# IP6518C.net
KiCad netlist of a schematic drawn in Altium Designer
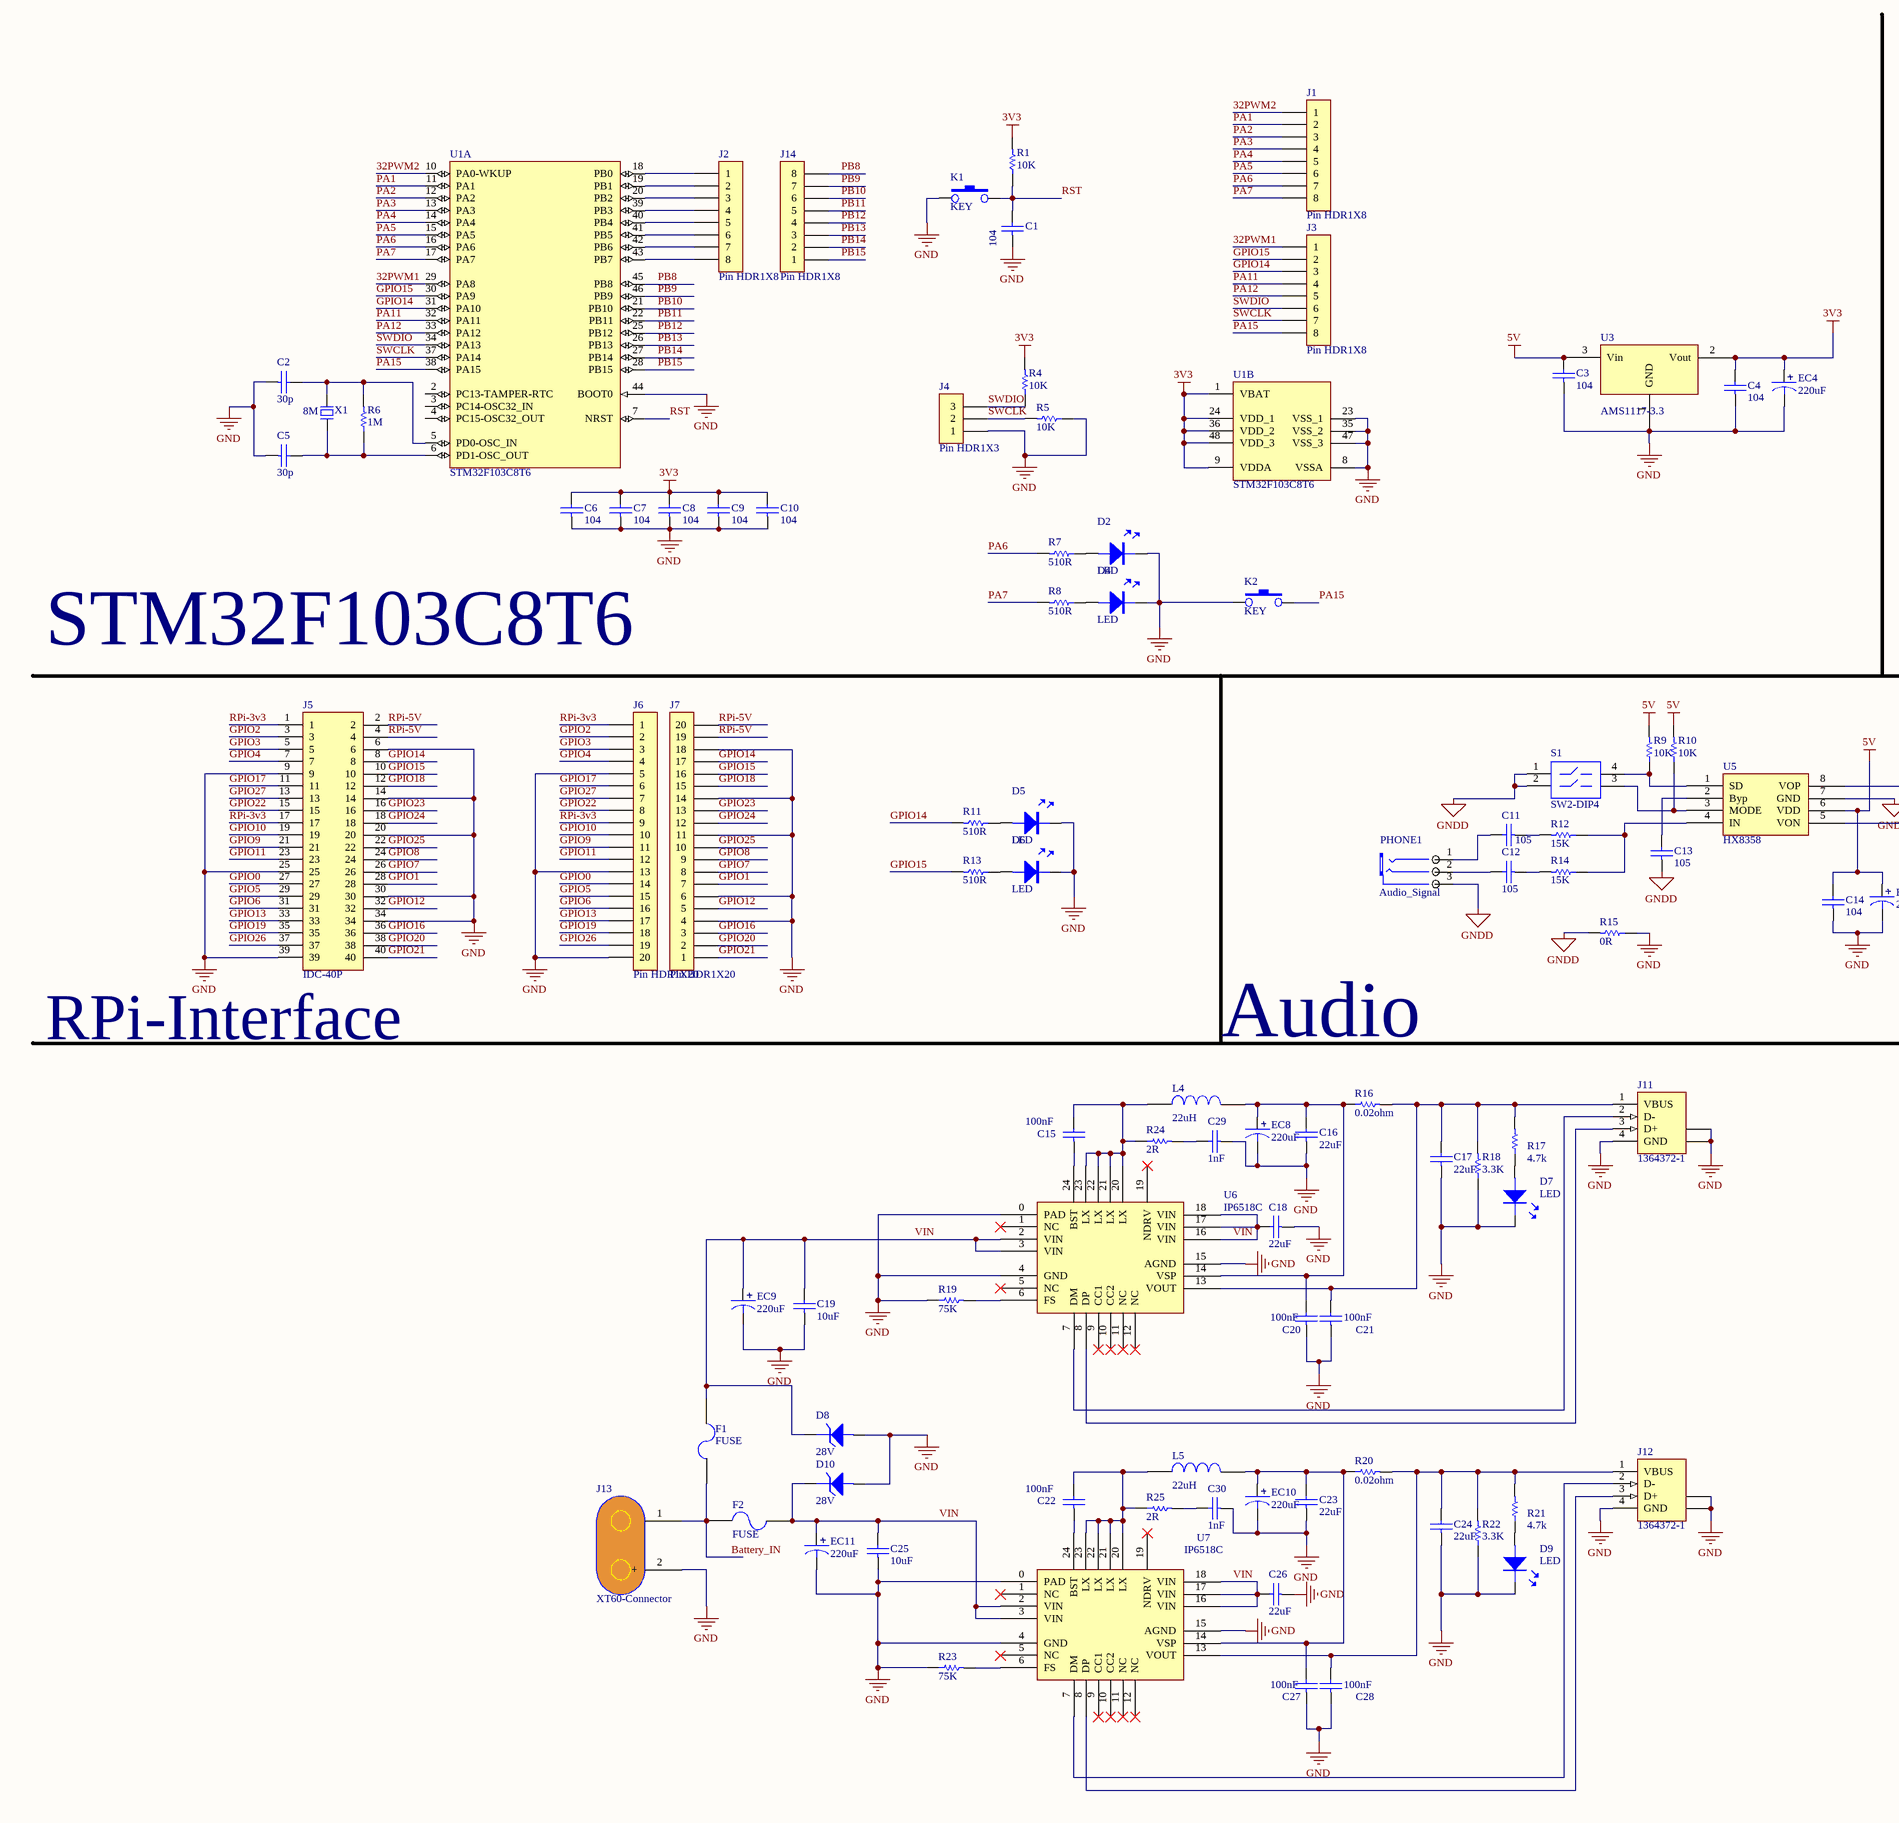
[diagram p0: IP6518C供电.SchDoc, left]
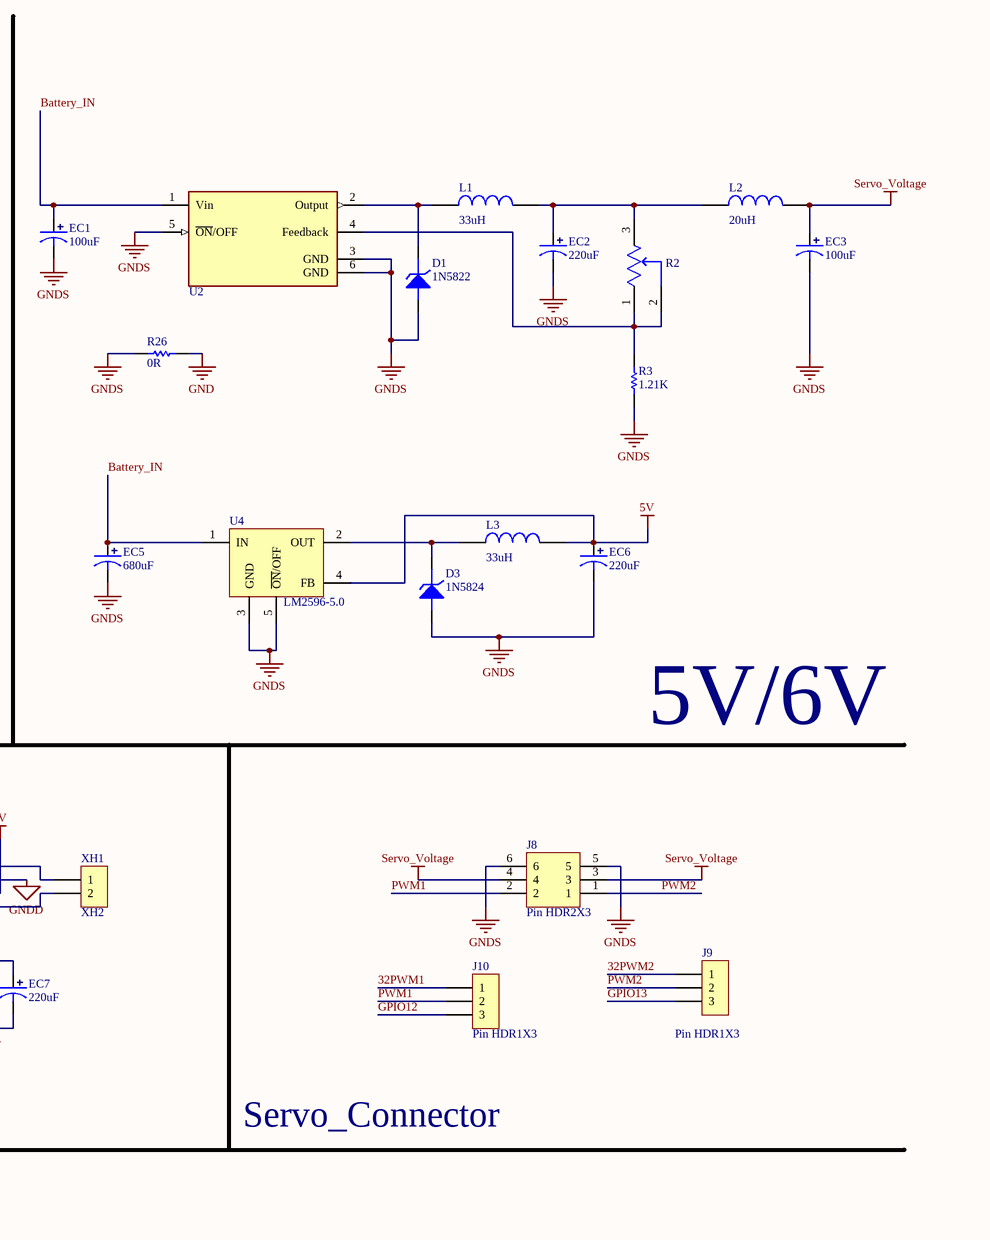
[diagram p1: IP6518C供电.SchDoc, right]

(export (version "E")
  (design (tool "Eeschema 10.0.6"))
  (components
    (comp (ref "C1")
      (value "104")
      (footprint "0805C")
      (description "无极性电容")
      (libsource (lib "电容") (part "CAP"))
    )
    (comp (ref "C2")
      (value "30p")
      (footprint "0805C")
      (description "无极性电容")
      (libsource (lib "电容") (part "CAP"))
    )
    (comp (ref "C3")
      (value "104")
      (footprint "0805C")
      (description "无极性电容")
      (libsource (lib "电容") (part "CAP"))
    )
    (comp (ref "C4")
      (value "104")
      (footprint "0805C")
      (description "无极性电容")
      (libsource (lib "电容") (part "CAP"))
    )
    (comp (ref "C5")
      (value "30p")
      (footprint "0805C")
      (description "无极性电容")
      (libsource (lib "电容") (part "CAP"))
    )
    (comp (ref "C6")
      (value "104")
      (footprint "0805C")
      (description "无极性电容")
      (libsource (lib "电容") (part "CAP"))
    )
    (comp (ref "C7")
      (value "104")
      (footprint "0805C")
      (description "无极性电容")
      (libsource (lib "电容") (part "CAP"))
    )
    (comp (ref "C8")
      (value "104")
      (footprint "0805C")
      (description "无极性电容")
      (libsource (lib "电容") (part "CAP"))
    )
    (comp (ref "C9")
      (value "104")
      (footprint "0805C")
      (description "无极性电容")
      (libsource (lib "电容") (part "CAP"))
    )
    (comp (ref "C10")
      (value "104")
      (footprint "0805C")
      (description "无极性电容")
      (libsource (lib "电容") (part "CAP"))
    )
    (comp (ref "C11")
      (value "105")
      (footprint "0805C")
      (description "无极性电容")
      (libsource (lib "电容") (part "CAP"))
    )
    (comp (ref "C12")
      (value "105")
      (footprint "0805C")
      (description "无极性电容")
      (libsource (lib "电容") (part "CAP"))
    )
    (comp (ref "C13")
      (value "105")
      (footprint "0805C")
      (description "无极性电容")
      (libsource (lib "电容") (part "CAP"))
    )
    (comp (ref "C14")
      (value "104")
      (footprint "0805C")
      (description "无极性电容")
      (libsource (lib "电容") (part "CAP"))
    )
    (comp (ref "C15")
      (value "100nF")
      (footprint "0805C")
      (description "无极性电容")
      (libsource (lib "电容") (part "CAP"))
    )
    (comp (ref "C16")
      (value "22uF")
      (footprint "1206C")
      (description "无极性电容")
      (libsource (lib "电容") (part "CAP"))
    )
    (comp (ref "C17")
      (value "22uF")
      (footprint "1206C")
      (description "无极性电容")
      (libsource (lib "电容") (part "CAP"))
    )
    (comp (ref "C18")
      (value "22uF")
      (footprint "1206C")
      (description "无极性电容")
      (libsource (lib "电容") (part "CAP"))
    )
    (comp (ref "C19")
      (value "10uF")
      (footprint "1206C")
      (description "无极性电容")
      (libsource (lib "电容") (part "CAP"))
    )
    (comp (ref "C20")
      (value "100nF")
      (footprint "0805C")
      (description "无极性电容")
      (libsource (lib "电容") (part "CAP"))
    )
    (comp (ref "C21")
      (value "100nF")
      (footprint "0805C")
      (description "无极性电容")
      (libsource (lib "电容") (part "CAP"))
    )
    (comp (ref "C22")
      (value "100nF")
      (footprint "0805C")
      (description "无极性电容")
      (libsource (lib "电容") (part "CAP"))
    )
    (comp (ref "C23")
      (value "22uF")
      (footprint "1206C")
      (description "无极性电容")
      (libsource (lib "电容") (part "CAP"))
    )
    (comp (ref "C24")
      (value "22uF")
      (footprint "1206C")
      (description "无极性电容")
      (libsource (lib "电容") (part "CAP"))
    )
    (comp (ref "C25")
      (value "10uF")
      (footprint "1206C")
      (description "无极性电容")
      (libsource (lib "电容") (part "CAP"))
    )
    (comp (ref "C26")
      (value "22uF")
      (footprint "1206C")
      (description "无极性电容")
      (libsource (lib "电容") (part "CAP"))
    )
    (comp (ref "C27")
      (value "100nF")
      (footprint "0805C")
      (description "无极性电容")
      (libsource (lib "电容") (part "CAP"))
    )
    (comp (ref "C28")
      (value "100nF")
      (footprint "0805C")
      (description "无极性电容")
      (libsource (lib "电容") (part "CAP"))
    )
    (comp (ref "C29")
      (value "1nF")
      (footprint "0805C")
      (description "无极性电容")
      (libsource (lib "电容") (part "CAP"))
    )
    (comp (ref "C30")
      (value "1nF")
      (footprint "0805C")
      (description "无极性电容")
      (libsource (lib "电容") (part "CAP"))
    )
    (comp (ref "D1")
      (value "1N5822")
      (footprint "SMA/DO-214AC")
      (description "稳压二极管")
      (libsource (lib "二极管") (part "DIODE ZENER"))
    )
    (comp (ref "D2") (value "LED") (footprint "LED-0805R") (libsource (lib "LED") (part "LED")))
    (comp (ref "D3")
      (value "1N5824")
      (footprint "SMA/DO-214AC")
      (description "稳压二极管")
      (libsource (lib "二极管") (part "DIODE ZENER"))
    )
    (comp (ref "D4") (value "LED") (footprint "LED-0805R") (libsource (lib "LED") (part "LED")))
    (comp (ref "D5") (value "LED") (footprint "LED-0805R") (libsource (lib "LED") (part "LED")))
    (comp (ref "D6") (value "LED") (footprint "LED-0805R") (libsource (lib "LED") (part "LED")))
    (comp (ref "D7") (value "LED") (footprint "LED-0805R") (libsource (lib "LED") (part "LED")))
    (comp (ref "D8")
      (value "28V")
      (footprint "SMA/DO-214AC")
      (description "稳压二极管")
      (libsource (lib "二极管") (part "DIODE ZENER"))
    )
    (comp (ref "D9") (value "LED") (footprint "LED-0805R") (libsource (lib "LED") (part "LED")))
    (comp (ref "D10")
      (value "28V")
      (footprint "SMA/DO-214AC")
      (description "稳压二极管")
      (libsource (lib "二极管") (part "DIODE ZENER"))
    )
    (comp (ref "EC1")
      (value "100uF")
      (footprint "SMD-EC6.3X6.3X10")
      (description "贴片电解电容")
      (libsource (lib "电容") (part "SMD_ECAP"))
    )
    (comp (ref "EC2")
      (value "220uF")
      (footprint "SMD-EC8X8X10")
      (description "贴片电解电容")
      (libsource (lib "电容") (part "SMD_ECAP"))
    )
    (comp (ref "EC3")
      (value "100uF")
      (footprint "SMD-EC6.3X6.3X10")
      (description "贴片电解电容")
      (libsource (lib "电容") (part "SMD_ECAP"))
    )
    (comp (ref "EC4")
      (value "220uF")
      (footprint "SMD-EC8X8X10")
      (description "贴片电解电容")
      (libsource (lib "电容") (part "SMD_ECAP"))
    )
    (comp (ref "EC5")
      (value "680uF")
      (footprint "DIP-EC10X17")
      (description "贴片电解电容")
      (libsource (lib "电容") (part "SMD_ECAP"))
    )
    (comp (ref "EC6")
      (value "220uF")
      (footprint "SMD-EC8X8X10")
      (description "贴片电解电容")
      (libsource (lib "电容") (part "SMD_ECAP"))
    )
    (comp (ref "EC7")
      (value "220uF")
      (footprint "SMD-EC8X8X10")
      (description "贴片电解电容")
      (libsource (lib "电容") (part "SMD_ECAP"))
    )
    (comp (ref "EC8")
      (value "220uF")
      (footprint "SMD-EC8X8X10")
      (description "贴片电解电容")
      (libsource (lib "电容") (part "SMD_ECAP"))
    )
    (comp (ref "EC9")
      (value "220uF")
      (footprint "SMD-EC10X10X10")
      (description "贴片电解电容")
      (libsource (lib "电容") (part "SMD_ECAP"))
    )
    (comp (ref "EC10")
      (value "220uF")
      (footprint "SMD-EC8X8X10")
      (description "贴片电解电容")
      (libsource (lib "电容") (part "SMD_ECAP"))
    )
    (comp (ref "EC11")
      (value "220uF")
      (footprint "SMD-EC10X10X10")
      (description "贴片电解电容")
      (libsource (lib "电容") (part "SMD_ECAP"))
    )
    (comp (ref "F1") (value "FUSE") (footprint "FUSE-1812") (libsource (lib "保险丝") (part "FUSE")))
    (comp (ref "F2") (value "FUSE") (footprint "FUSE-1812") (libsource (lib "保险丝") (part "FUSE")))
    (comp (ref "J1")
      (value "Pin HDR1X8")
      (footprint "Pin HDR1X8/2.54mm-S")
      (libsource (lib "排针") (part "Pin HDR1X8"))
    )
    (comp (ref "J2")
      (value "Pin HDR1X8")
      (footprint "Pin HDR1X8/2.54mm-S")
      (libsource (lib "排针") (part "Pin HDR1X8"))
    )
    (comp (ref "J3")
      (value "Pin HDR1X8")
      (footprint "Pin HDR1X8/2.54mm-S")
      (libsource (lib "排针") (part "Pin HDR1X8"))
    )
    (comp (ref "J4")
      (value "Pin HDR1X3")
      (footprint "Pin HDR1X3/2.54mm-S")
      (libsource (lib "排针") (part "Pin HDR1X3"))
    )
    (comp (ref "J5") (value "IDC-40P") (footprint "IDC2.54-40P") (libsource (lib "简易牛角座") (part "IDC-40P")))
    (comp (ref "J6")
      (value "Pin HDR1X20")
      (footprint "Pin HDR1X20/2.54mm-S")
      (libsource (lib "排针") (part "Pin HDR1X20"))
    )
    (comp (ref "J7")
      (value "Pin HDR1X20")
      (footprint "Pin HDR1X20/2.54mm-S")
      (libsource (lib "") (part "Pin HDR1X20_1"))
    )
    (comp (ref "J8")
      (value "Pin HDR2X3")
      (footprint "Pin HDR2X3/2.54mm-S")
      (libsource (lib "排针") (part "Pin HDR2X3"))
    )
    (comp (ref "J9")
      (value "Pin HDR1X3")
      (footprint "Pin HDR1X3/2.54mm-S")
      (libsource (lib "") (part "Pin HDR1X3_1"))
    )
    (comp (ref "J10")
      (value "Pin HDR1X3")
      (footprint "Pin HDR1X3/2.54mm-S")
      (libsource (lib "") (part "Pin HDR1X3_1"))
    )
    (comp (ref "J11")
      (value "1364372-1")
      (footprint "440068")
      (description "USB 1.1, Right Angle, Thru-Hole, A Type, Receptacle, 4 Position, Black")
      (fields (field (name "PUBLISHER") "Altium Limited"))
      (libsource (lib "USB") (part "1364372-1"))
    )
    (comp (ref "J12")
      (value "1364372-1")
      (footprint "440068")
      (description "USB 1.1, Right Angle, Thru-Hole, A Type, Receptacle, 4 Position, Black")
      (fields (field (name "PUBLISHER") "Altium Limited"))
      (libsource (lib "USB") (part "1364372-1"))
    )
    (comp (ref "J13")
      (value "XT60-Connector")
      (footprint "TX60PW-M20")
      (description "对于母头，+-对调")
      (libsource (lib "XT60") (part "Component_1"))
    )
    (comp (ref "J14")
      (value "Pin HDR1X8")
      (footprint "Pin HDR1X8/2.54mm-S")
      (libsource (lib "") (part "Pin HDR1X8_1"))
    )
    (comp (ref "K1") (value "KEY") (footprint "SMD-3X6X4.3") (libsource (lib "轻触开关") (part "KEY")))
    (comp (ref "K2") (value "KEY") (footprint "SMD-3X6X4.3") (libsource (lib "轻触开关") (part "KEY")))
    (comp (ref "L1")
      (value "33uH")
      (footprint "CDRH74")
      (description "INDUCTOR")
      (libsource (lib "电感") (part "INDUCTOR"))
    )
    (comp (ref "L2")
      (value "20uH")
      (footprint "CDRH74")
      (description "INDUCTOR")
      (libsource (lib "电感") (part "INDUCTOR"))
    )
    (comp (ref "L3")
      (value "33uH")
      (footprint "CDRH74")
      (description "INDUCTOR")
      (libsource (lib "电感") (part "INDUCTOR"))
    )
    (comp (ref "L4")
      (value "22uH")
      (footprint "CDRH127")
      (description "INDUCTOR")
      (libsource (lib "电感") (part "INDUCTOR"))
    )
    (comp (ref "L5")
      (value "22uH")
      (footprint "CDRH129")
      (description "INDUCTOR")
      (libsource (lib "电感") (part "INDUCTOR"))
    )
    (comp (ref "PHONE1")
      (value "Audio_Signal")
      (footprint "PHONE_ST")
      (libsource (lib "音频插座") (part "PHONE_M"))
    )
    (comp (ref "R1") (value "10K") (footprint "0805R") (libsource (lib "电阻") (part "RES")))
    (comp (ref "R2")
      (value "3296W-1-504LF 50K")
      (footprint "Bourns_3296W_MFG")
      (description "RES TRIMMER 50K OHM 0.5W PC PIN TOP")
      (fields (field (name "DIGIKEY PART NUMBER") "3296W-504LF-ND") (field (name "MANUFACTURER") "Bourns"))
      (libsource (lib "EEConcierge") (part "3296W-1-504LF"))
    )
    (comp (ref "R3") (value "1.21K") (footprint "0805R") (libsource (lib "电阻") (part "RES")))
    (comp (ref "R4") (value "10K") (footprint "0805R") (libsource (lib "电阻") (part "RES")))
    (comp (ref "R5") (value "10K") (footprint "0805R") (libsource (lib "电阻") (part "RES")))
    (comp (ref "R6") (value "1M") (footprint "0805R") (libsource (lib "电阻") (part "RES")))
    (comp (ref "R7") (value "510R") (footprint "0805R") (libsource (lib "电阻") (part "RES")))
    (comp (ref "R8") (value "510R") (footprint "0805R") (libsource (lib "电阻") (part "RES")))
    (comp (ref "R9") (value "10K") (footprint "0805R") (libsource (lib "电阻") (part "RES")))
    (comp (ref "R10") (value "10K") (footprint "0805R") (libsource (lib "电阻") (part "RES")))
    (comp (ref "R11") (value "510R") (footprint "0805R") (libsource (lib "电阻") (part "RES")))
    (comp (ref "R12") (value "15K") (footprint "0805R") (libsource (lib "电阻") (part "RES")))
    (comp (ref "R13") (value "510R") (footprint "0805R") (libsource (lib "电阻") (part "RES")))
    (comp (ref "R14") (value "15K") (footprint "0805R") (libsource (lib "电阻") (part "RES")))
    (comp (ref "R15") (value "0R") (footprint "0805R") (libsource (lib "电阻") (part "RES")))
    (comp (ref "R16") (value "0.02ohm") (footprint "1206R") (libsource (lib "电阻") (part "RES")))
    (comp (ref "R17") (value "4.7k") (footprint "0805R") (libsource (lib "电阻") (part "RES")))
    (comp (ref "R18") (value "3.3K") (footprint "0805R") (libsource (lib "电阻") (part "RES")))
    (comp (ref "R19") (value "75K") (footprint "0805R") (libsource (lib "电阻") (part "RES")))
    (comp (ref "R20") (value "0.02ohm") (footprint "1206R") (libsource (lib "电阻") (part "RES")))
    (comp (ref "R21") (value "4.7k") (footprint "0805R") (libsource (lib "电阻") (part "RES")))
    (comp (ref "R22") (value "3.3K") (footprint "0805R") (libsource (lib "电阻") (part "RES")))
    (comp (ref "R23") (value "75K") (footprint "0805R") (libsource (lib "电阻") (part "RES")))
    (comp (ref "R24") (value "2R") (footprint "0805R") (libsource (lib "电阻") (part "RES")))
    (comp (ref "R25") (value "2R") (footprint "0805R") (libsource (lib "电阻") (part "RES")))
    (comp (ref "R26") (value "0R") (footprint "0805R") (libsource (lib "电阻") (part "RES")))
    (comp (ref "S1") (value "SW2-DIP4") (footprint "DIP-Switch2") (libsource (lib "拨码开关") (part "SW2-DIP4")))
    (comp (ref "U1")
      (value "STM32F103C8T6")
      (footprint "STM-LQFP48_N")
      (libsource (lib "STMicroelectronics STM32 F1") (part "STM32F103C8T6"))
    )
    (comp (ref "U2")
      (value "LM2596DSADJG")
      (footprint "ON_Semiconductor_936A-02_MFG")
      (description "IC REG MULT CONFG ADJ 3A D2PAK-5")
      (fields
        (field (name "DIGIKEY PART NUMBER") "LM2596DSADJGOS-ND")
        (field (name "MANUFACTURER") "ON Semiconductor")
      )
      (libsource (lib "EEConcierge") (part "LM2596DSADJG"))
    )
    (comp (ref "U3")
      (value "AMS1117-3.3")
      (footprint "SOT223")
      (description "三端稳压芯片")
      (libsource (lib "电源芯片") (part "AMS1117"))
    )
    (comp (ref "U4")
      (value "LM2596-5.0")
      (footprint "TO263-5A")
      (description "DC降压芯片")
      (libsource (lib "电源芯片") (part "LM2596-5.0"))
    )
    (comp (ref "U5") (value "HX8358") (footprint "SOP8-9") (libsource (lib "HX8358") (part "HX8358")))
    (comp (ref "U6") (value "IP6518C") (footprint "QFN24") (libsource (lib "IP6518C") (part "IP6518C")))
    (comp (ref "U7") (value "IP6518C") (footprint "QFN24") (libsource (lib "IP6518C") (part "IP6518C")))
    (comp (ref "X1")
      (value "8M")
      (footprint "OSC HC-49SMD")
      (description "2脚无源脚晶振")
      (libsource (lib "晶振") (part "XTAL-2P"))
    )
    (comp (ref "XH1") (value "XH2") (footprint "XH2/2.54mm/90") (libsource (lib "XH，VH") (part "XH2")))
  )
  (nets
    (net (code "1") (name "/32PWM1") (class "Default")
      (node (ref "J10") (pin "1") (pinfunction "1_1") (pintype "passive"))
      (node (ref "J3") (pin "1") (pinfunction "1_1") (pintype "passive"))
      (node (ref "U1") (pin "29") (pinfunction "PA8_29") (pintype "bidirectional"))
    )
    (net (code "2") (name "/32PWM2") (class "Default")
      (node (ref "J1") (pin "1") (pinfunction "1_1") (pintype "passive"))
      (node (ref "J9") (pin "1") (pinfunction "1_1") (pintype "passive"))
      (node (ref "U1") (pin "10") (pinfunction "PA0-WKUP_10") (pintype "bidirectional"))
    )
    (net (code "3") (name "/Battery_IN") (class "Default")
      (node (ref "EC1") (pin "1") (pinfunction "1_1") (pintype "passive"))
      (node (ref "EC5") (pin "1") (pinfunction "1_1") (pintype "passive"))
      (node (ref "F1") (pin "1") (pinfunction "1_1") (pintype "passive"))
      (node (ref "F2") (pin "2") (pinfunction "2_2") (pintype "passive"))
      (node (ref "J13") (pin "1") (pintype "passive"))
      (node (ref "U2") (pin "1") (pinfunction "Vin_1") (pintype "power_in"))
      (node (ref "U4") (pin "1") (pinfunction "IN_1") (pintype "power_in"))
    )
    (net (code "4") (name "/GPIO0") (class "Default")
      (node (ref "J5") (pin "27") (pinfunction "27_27") (pintype "passive"))
      (node (ref "J6") (pin "14") (pinfunction "14_14") (pintype "passive"))
    )
    (net (code "5") (name "/GPIO1") (class "Default")
      (node (ref "J5") (pin "28") (pinfunction "28_28") (pintype "passive"))
      (node (ref "J7") (pin "7") (pinfunction "7_7") (pintype "passive"))
    )
    (net (code "6") (name "/GPIO2") (class "Default")
      (node (ref "J5") (pin "3") (pinfunction "3_3") (pintype "passive"))
      (node (ref "J6") (pin "2") (pinfunction "2_2") (pintype "passive"))
    )
    (net (code "7") (name "/GPIO3") (class "Default")
      (node (ref "J5") (pin "5") (pinfunction "5_5") (pintype "passive"))
      (node (ref "J6") (pin "3") (pinfunction "3_3") (pintype "passive"))
    )
    (net (code "8") (name "/GPIO4") (class "Default")
      (node (ref "J5") (pin "7") (pinfunction "7_7") (pintype "passive"))
      (node (ref "J6") (pin "4") (pinfunction "4_4") (pintype "passive"))
    )
    (net (code "9") (name "/GPIO5") (class "Default")
      (node (ref "J5") (pin "29") (pinfunction "29_29") (pintype "passive"))
      (node (ref "J6") (pin "15") (pinfunction "15_15") (pintype "passive"))
    )
    (net (code "10") (name "/GPIO6") (class "Default")
      (node (ref "J5") (pin "31") (pinfunction "31_31") (pintype "passive"))
      (node (ref "J6") (pin "16") (pinfunction "16_16") (pintype "passive"))
    )
    (net (code "11") (name "/GPIO7") (class "Default")
      (node (ref "J5") (pin "26") (pinfunction "26_26") (pintype "passive"))
      (node (ref "J7") (pin "8") (pinfunction "8_8") (pintype "passive"))
    )
    (net (code "12") (name "/GPIO8") (class "Default")
      (node (ref "J5") (pin "24") (pinfunction "24_24") (pintype "passive"))
      (node (ref "J7") (pin "9") (pinfunction "9_9") (pintype "passive"))
    )
    (net (code "13") (name "/GPIO9") (class "Default")
      (node (ref "J5") (pin "21") (pinfunction "21_21") (pintype "passive"))
      (node (ref "J6") (pin "11") (pinfunction "11_11") (pintype "passive"))
    )
    (net (code "14") (name "/GPIO10") (class "Default")
      (node (ref "J5") (pin "19") (pinfunction "19_19") (pintype "passive"))
      (node (ref "J6") (pin "10") (pinfunction "10_10") (pintype "passive"))
    )
    (net (code "15") (name "/GPIO11") (class "Default")
      (node (ref "J5") (pin "23") (pinfunction "23_23") (pintype "passive"))
      (node (ref "J6") (pin "12") (pinfunction "12_12") (pintype "passive"))
    )
    (net (code "16") (name "/GPIO12") (class "Default")
      (node (ref "J10") (pin "3") (pinfunction "3_3") (pintype "passive"))
      (node (ref "J5") (pin "32") (pinfunction "32_32") (pintype "passive"))
      (node (ref "J7") (pin "5") (pinfunction "5_5") (pintype "passive"))
    )
    (net (code "17") (name "/GPIO13") (class "Default")
      (node (ref "J5") (pin "33") (pinfunction "33_33") (pintype "passive"))
      (node (ref "J6") (pin "17") (pinfunction "17_17") (pintype "passive"))
      (node (ref "J9") (pin "3") (pinfunction "3_3") (pintype "passive"))
    )
    (net (code "18") (name "/GPIO14") (class "Default")
      (node (ref "J3") (pin "3") (pinfunction "3_3") (pintype "passive"))
      (node (ref "J5") (pin "8") (pinfunction "8_8") (pintype "passive"))
      (node (ref "J7") (pin "17") (pinfunction "17_17") (pintype "passive"))
      (node (ref "R11") (pin "2") (pinfunction "2_2") (pintype "passive"))
      (node (ref "U1") (pin "31") (pinfunction "PA10_31") (pintype "bidirectional"))
    )
    (net (code "19") (name "/GPIO15") (class "Default")
      (node (ref "J3") (pin "2") (pinfunction "2_2") (pintype "passive"))
      (node (ref "J5") (pin "10") (pinfunction "10_10") (pintype "passive"))
      (node (ref "J7") (pin "16") (pinfunction "16_16") (pintype "passive"))
      (node (ref "R13") (pin "2") (pinfunction "2_2") (pintype "passive"))
      (node (ref "U1") (pin "30") (pinfunction "PA9_30") (pintype "bidirectional"))
    )
    (net (code "20") (name "/GPIO16") (class "Default")
      (node (ref "J5") (pin "36") (pinfunction "36_36") (pintype "passive"))
      (node (ref "J7") (pin "3") (pinfunction "3_3") (pintype "passive"))
    )
    (net (code "21") (name "/GPIO17") (class "Default")
      (node (ref "J5") (pin "11") (pinfunction "11_11") (pintype "passive"))
      (node (ref "J6") (pin "6") (pinfunction "6_6") (pintype "passive"))
    )
    (net (code "22") (name "/GPIO18") (class "Default")
      (node (ref "J5") (pin "12") (pinfunction "12_12") (pintype "passive"))
      (node (ref "J7") (pin "15") (pinfunction "15_15") (pintype "passive"))
    )
    (net (code "23") (name "/GPIO19") (class "Default")
      (node (ref "J5") (pin "35") (pinfunction "35_35") (pintype "passive"))
      (node (ref "J6") (pin "18") (pinfunction "18_18") (pintype "passive"))
    )
    (net (code "24") (name "/GPIO20") (class "Default")
      (node (ref "J5") (pin "38") (pinfunction "38_38") (pintype "passive"))
      (node (ref "J7") (pin "2") (pinfunction "2_2") (pintype "passive"))
    )
    (net (code "25") (name "/GPIO21") (class "Default")
      (node (ref "J5") (pin "40") (pinfunction "40_40") (pintype "passive"))
      (node (ref "J7") (pin "1") (pinfunction "1_1") (pintype "passive"))
    )
    (net (code "26") (name "/GPIO22") (class "Default")
      (node (ref "J5") (pin "15") (pinfunction "15_15") (pintype "passive"))
      (node (ref "J6") (pin "8") (pinfunction "8_8") (pintype "passive"))
    )
    (net (code "27") (name "/GPIO23") (class "Default")
      (node (ref "J5") (pin "16") (pinfunction "16_16") (pintype "passive"))
      (node (ref "J7") (pin "13") (pinfunction "13_13") (pintype "passive"))
    )
    (net (code "28") (name "/GPIO24") (class "Default")
      (node (ref "J5") (pin "18") (pinfunction "18_18") (pintype "passive"))
      (node (ref "J7") (pin "12") (pinfunction "12_12") (pintype "passive"))
    )
    (net (code "29") (name "/GPIO25") (class "Default")
      (node (ref "J5") (pin "22") (pinfunction "22_22") (pintype "passive"))
      (node (ref "J7") (pin "10") (pinfunction "10_10") (pintype "passive"))
    )
    (net (code "30") (name "/GPIO26") (class "Default")
      (node (ref "J5") (pin "37") (pinfunction "37_37") (pintype "passive"))
      (node (ref "J6") (pin "19") (pinfunction "19_19") (pintype "passive"))
    )
    (net (code "31") (name "/GPIO27") (class "Default")
      (node (ref "J5") (pin "13") (pinfunction "13_13") (pintype "passive"))
      (node (ref "J6") (pin "7") (pinfunction "7_7") (pintype "passive"))
    )
    (net (code "32") (name "/PA1") (class "Default")
      (node (ref "J1") (pin "2") (pinfunction "2_2") (pintype "passive"))
      (node (ref "U1") (pin "11") (pinfunction "PA1_11") (pintype "bidirectional"))
    )
    (net (code "33") (name "/PA2") (class "Default")
      (node (ref "J1") (pin "3") (pinfunction "3_3") (pintype "passive"))
      (node (ref "U1") (pin "12") (pinfunction "PA2_12") (pintype "bidirectional"))
    )
    (net (code "34") (name "/PA3") (class "Default")
      (node (ref "J1") (pin "4") (pinfunction "4_4") (pintype "passive"))
      (node (ref "U1") (pin "13") (pinfunction "PA3_13") (pintype "bidirectional"))
    )
    (net (code "35") (name "/PA4") (class "Default")
      (node (ref "J1") (pin "5") (pinfunction "5_5") (pintype "passive"))
      (node (ref "U1") (pin "14") (pinfunction "PA4_14") (pintype "bidirectional"))
    )
    (net (code "36") (name "/PA5") (class "Default")
      (node (ref "J1") (pin "6") (pinfunction "6_6") (pintype "passive"))
      (node (ref "U1") (pin "15") (pinfunction "PA5_15") (pintype "bidirectional"))
    )
    (net (code "37") (name "/PA6") (class "Default")
      (node (ref "J1") (pin "7") (pinfunction "7_7") (pintype "passive"))
      (node (ref "R7") (pin "2") (pinfunction "2_2") (pintype "passive"))
      (node (ref "U1") (pin "16") (pinfunction "PA6_16") (pintype "bidirectional"))
    )
    (net (code "38") (name "/PA7") (class "Default")
      (node (ref "J1") (pin "8") (pinfunction "8_8") (pintype "passive"))
      (node (ref "R8") (pin "2") (pinfunction "2_2") (pintype "passive"))
      (node (ref "U1") (pin "17") (pinfunction "PA7_17") (pintype "bidirectional"))
    )
    (net (code "39") (name "/PA11") (class "Default")
      (node (ref "J3") (pin "4") (pinfunction "4_4") (pintype "passive"))
      (node (ref "U1") (pin "32") (pinfunction "PA11_32") (pintype "bidirectional"))
    )
    (net (code "40") (name "/PA12") (class "Default")
      (node (ref "J3") (pin "5") (pinfunction "5_5") (pintype "passive"))
      (node (ref "U1") (pin "33") (pinfunction "PA12_33") (pintype "bidirectional"))
    )
    (net (code "41") (name "/PA15") (class "Default")
      (node (ref "J3") (pin "8") (pinfunction "8_8") (pintype "passive"))
      (node (ref "K2") (pin "3") (pinfunction "3_3") (pintype "passive"))
      (node (ref "U1") (pin "38") (pinfunction "PA15_38") (pintype "bidirectional"))
    )
    (net (code "42") (name "/PB8") (class "Default")
      (node (ref "J14") (pin "8") (pinfunction "8_8") (pintype "passive"))
      (node (ref "U1") (pin "45") (pinfunction "PB8_45") (pintype "bidirectional"))
    )
    (net (code "43") (name "/PB9") (class "Default")
      (node (ref "J14") (pin "7") (pinfunction "7_7") (pintype "passive"))
      (node (ref "U1") (pin "46") (pinfunction "PB9_46") (pintype "bidirectional"))
    )
    (net (code "44") (name "/PB10") (class "Default")
      (node (ref "J14") (pin "6") (pinfunction "6_6") (pintype "passive"))
      (node (ref "U1") (pin "21") (pinfunction "PB10_21") (pintype "bidirectional"))
    )
    (net (code "45") (name "/PB11") (class "Default")
      (node (ref "J14") (pin "5") (pinfunction "5_5") (pintype "passive"))
      (node (ref "U1") (pin "22") (pinfunction "PB11_22") (pintype "bidirectional"))
    )
    (net (code "46") (name "/PB12") (class "Default")
      (node (ref "J14") (pin "4") (pinfunction "4_4") (pintype "passive"))
      (node (ref "U1") (pin "25") (pinfunction "PB12_25") (pintype "bidirectional"))
    )
    (net (code "47") (name "/PB13") (class "Default")
      (node (ref "J14") (pin "3") (pinfunction "3_3") (pintype "passive"))
      (node (ref "U1") (pin "26") (pinfunction "PB13_26") (pintype "bidirectional"))
    )
    (net (code "48") (name "/PB14") (class "Default")
      (node (ref "J14") (pin "2") (pinfunction "2_2") (pintype "passive"))
      (node (ref "U1") (pin "27") (pinfunction "PB14_27") (pintype "bidirectional"))
    )
    (net (code "49") (name "/PB15") (class "Default")
      (node (ref "J14") (pin "1") (pinfunction "1_1") (pintype "passive"))
      (node (ref "U1") (pin "28") (pinfunction "PB15_28") (pintype "bidirectional"))
    )
    (net (code "50") (name "/PWM1") (class "Default")
      (node (ref "J10") (pin "2") (pinfunction "2_2") (pintype "passive"))
      (node (ref "J8") (pin "2") (pinfunction "2_2") (pintype "passive"))
    )
    (net (code "51") (name "/PWM2") (class "Default")
      (node (ref "J8") (pin "1") (pinfunction "1_1") (pintype "passive"))
      (node (ref "J9") (pin "2") (pinfunction "2_2") (pintype "passive"))
    )
    (net (code "52") (name "/RPi-3v3") (class "Default")
      (node (ref "J5") (pin "1") (pinfunction "1_1") (pintype "passive"))
      (node (ref "J5") (pin "17") (pinfunction "17_17") (pintype "passive"))
      (node (ref "J6") (pin "1") (pinfunction "1_1") (pintype "passive"))
      (node (ref "J6") (pin "9") (pinfunction "9_9") (pintype "passive"))
    )
    (net (code "53") (name "/RPi-5V") (class "Default")
      (node (ref "J5") (pin "2") (pinfunction "2_2") (pintype "passive"))
      (node (ref "J5") (pin "4") (pinfunction "4_4") (pintype "passive"))
      (node (ref "J7") (pin "19") (pinfunction "19_19") (pintype "passive"))
      (node (ref "J7") (pin "20") (pinfunction "20_20") (pintype "passive"))
    )
    (net (code "54") (name "/RST") (class "Default")
      (node (ref "C1") (pin "2") (pinfunction "2_2") (pintype "passive"))
      (node (ref "K1") (pin "3") (pinfunction "3_3") (pintype "passive"))
      (node (ref "R1") (pin "1") (pinfunction "1_1") (pintype "passive"))
      (node (ref "U1") (pin "7") (pinfunction "NRST_7") (pintype "bidirectional"))
    )
    (net (code "55") (name "/SWCLK") (class "Default")
      (node (ref "J3") (pin "7") (pinfunction "7_7") (pintype "passive"))
      (node (ref "J4") (pin "2") (pinfunction "2_2") (pintype "passive"))
      (node (ref "R5") (pin "2") (pinfunction "2_2") (pintype "passive"))
      (node (ref "U1") (pin "37") (pinfunction "PA14_37") (pintype "bidirectional"))
    )
    (net (code "56") (name "/SWDIO") (class "Default")
      (node (ref "J3") (pin "6") (pinfunction "6_6") (pintype "passive"))
      (node (ref "J4") (pin "3") (pinfunction "3_3") (pintype "passive"))
      (node (ref "R4") (pin "1") (pinfunction "1_1") (pintype "passive"))
      (node (ref "U1") (pin "34") (pinfunction "PA13_34") (pintype "bidirectional"))
    )
    (net (code "57") (name "/VIN") (class "Default")
      (node (ref "C18") (pin "2") (pinfunction "2_2") (pintype "passive"))
      (node (ref "C19") (pin "2") (pinfunction "2_2") (pintype "passive"))
      (node (ref "C25") (pin "2") (pinfunction "2_2") (pintype "passive"))
      (node (ref "C26") (pin "2") (pinfunction "2_2") (pintype "passive"))
      (node (ref "D10") (pin "K") (pinfunction "K_K") (pintype "passive"))
      (node (ref "D8") (pin "K") (pinfunction "K_K") (pintype "passive"))
      (node (ref "EC11") (pin "1") (pinfunction "1_1") (pintype "passive"))
      (node (ref "EC9") (pin "1") (pinfunction "1_1") (pintype "passive"))
      (node (ref "F1") (pin "2") (pinfunction "2_2") (pintype "passive"))
      (node (ref "F2") (pin "1") (pinfunction "1_1") (pintype "passive"))
      (node (ref "U6") (pin "16") (pinfunction "VIN_16") (pintype "passive"))
      (node (ref "U6") (pin "17") (pinfunction "VIN_17") (pintype "passive"))
      (node (ref "U6") (pin "18") (pinfunction "VIN_18") (pintype "passive"))
      (node (ref "U6") (pin "2") (pinfunction "VIN_2") (pintype "passive"))
      (node (ref "U6") (pin "3") (pinfunction "VIN_3") (pintype "passive"))
      (node (ref "U7") (pin "16") (pinfunction "VIN_16") (pintype "passive"))
      (node (ref "U7") (pin "17") (pinfunction "VIN_17") (pintype "passive"))
      (node (ref "U7") (pin "18") (pinfunction "VIN_18") (pintype "passive"))
      (node (ref "U7") (pin "2") (pinfunction "VIN_2") (pintype "passive"))
      (node (ref "U7") (pin "3") (pinfunction "VIN_3") (pintype "passive"))
    )
    (net (code "58") (name "3V3") (class "Default")
      (node (ref "C10") (pin "2") (pinfunction "2_2") (pintype "passive"))
      (node (ref "C4") (pin "2") (pinfunction "2_2") (pintype "passive"))
      (node (ref "C6") (pin "2") (pinfunction "2_2") (pintype "passive"))
      (node (ref "C7") (pin "2") (pinfunction "2_2") (pintype "passive"))
      (node (ref "C8") (pin "2") (pinfunction "2_2") (pintype "passive"))
      (node (ref "C9") (pin "2") (pinfunction "2_2") (pintype "passive"))
      (node (ref "EC4") (pin "1") (pinfunction "1_1") (pintype "passive"))
      (node (ref "R1") (pin "2") (pinfunction "2_2") (pintype "passive"))
      (node (ref "R4") (pin "2") (pinfunction "2_2") (pintype "passive"))
      (node (ref "U1") (pin "1") (pinfunction "VBAT_1") (pintype "power_in"))
      (node (ref "U1") (pin "24") (pinfunction "VDD_1_24") (pintype "power_in"))
      (node (ref "U1") (pin "36") (pinfunction "VDD_2_36") (pintype "power_in"))
      (node (ref "U1") (pin "48") (pinfunction "VDD_3_48") (pintype "power_in"))
      (node (ref "U1") (pin "9") (pinfunction "VDDA_9") (pintype "power_in"))
      (node (ref "U3") (pin "2") (pinfunction "Vout_2") (pintype "passive"))
    )
    (net (code "59") (name "5V") (class "Default")
      (node (ref "C14") (pin "2") (pinfunction "2_2") (pintype "passive"))
      (node (ref "C3") (pin "2") (pinfunction "2_2") (pintype "passive"))
      (node (ref "EC6") (pin "1") (pinfunction "1_1") (pintype "passive"))
      (node (ref "EC7") (pin "1") (pinfunction "1_1") (pintype "passive"))
      (node (ref "L3") (pin "2") (pinfunction "2_2") (pintype "passive"))
      (node (ref "R10") (pin "2") (pinfunction "2_2") (pintype "passive"))
      (node (ref "R9") (pin "2") (pinfunction "2_2") (pintype "passive"))
      (node (ref "U3") (pin "3") (pinfunction "Vin_3") (pintype "passive"))
      (node (ref "U4") (pin "4") (pinfunction "FB_4") (pintype "passive"))
      (node (ref "U5") (pin "6") (pinfunction "VDD_6") (pintype "passive"))
    )
    (net (code "60") (name "GND") (class "Default")
      (node (ref "C1") (pin "1") (pinfunction "1_1") (pintype "passive"))
      (node (ref "C10") (pin "1") (pinfunction "1_1") (pintype "passive"))
      (node (ref "C14") (pin "1") (pinfunction "1_1") (pintype "passive"))
      (node (ref "C16") (pin "1") (pinfunction "1_1") (pintype "passive"))
      (node (ref "C17") (pin "1") (pinfunction "1_1") (pintype "passive"))
      (node (ref "C18") (pin "1") (pinfunction "1_1") (pintype "passive"))
      (node (ref "C19") (pin "1") (pinfunction "1_1") (pintype "passive"))
      (node (ref "C2") (pin "1") (pinfunction "1_1") (pintype "passive"))
      (node (ref "C20") (pin "1") (pinfunction "1_1") (pintype "passive"))
      (node (ref "C21") (pin "1") (pinfunction "1_1") (pintype "passive"))
      (node (ref "C23") (pin "1") (pinfunction "1_1") (pintype "passive"))
      (node (ref "C24") (pin "1") (pinfunction "1_1") (pintype "passive"))
      (node (ref "C25") (pin "1") (pinfunction "1_1") (pintype "passive"))
      (node (ref "C26") (pin "1") (pinfunction "1_1") (pintype "passive"))
      (node (ref "C27") (pin "1") (pinfunction "1_1") (pintype "passive"))
      (node (ref "C28") (pin "1") (pinfunction "1_1") (pintype "passive"))
      (node (ref "C29") (pin "1") (pinfunction "1_1") (pintype "passive"))
      (node (ref "C3") (pin "1") (pinfunction "1_1") (pintype "passive"))
      (node (ref "C30") (pin "1") (pinfunction "1_1") (pintype "passive"))
      (node (ref "C4") (pin "1") (pinfunction "1_1") (pintype "passive"))
      (node (ref "C5") (pin "1") (pinfunction "1_1") (pintype "passive"))
      (node (ref "C6") (pin "1") (pinfunction "1_1") (pintype "passive"))
      (node (ref "C7") (pin "1") (pinfunction "1_1") (pintype "passive"))
      (node (ref "C8") (pin "1") (pinfunction "1_1") (pintype "passive"))
      (node (ref "C9") (pin "1") (pinfunction "1_1") (pintype "passive"))
      (node (ref "D10") (pin "A") (pinfunction "A_A") (pintype "passive"))
      (node (ref "D2") (pin "K") (pinfunction "K_K") (pintype "passive"))
      (node (ref "D4") (pin "K") (pinfunction "K_K") (pintype "passive"))
      (node (ref "D5") (pin "K") (pinfunction "K_K") (pintype "passive"))
      (node (ref "D6") (pin "K") (pinfunction "K_K") (pintype "passive"))
      (node (ref "D7") (pin "K") (pinfunction "K_K") (pintype "passive"))
      (node (ref "D8") (pin "A") (pinfunction "A_A") (pintype "passive"))
      (node (ref "D9") (pin "K") (pinfunction "K_K") (pintype "passive"))
      (node (ref "EC10") (pin "2") (pinfunction "2_2") (pintype "passive"))
      (node (ref "EC11") (pin "2") (pinfunction "2_2") (pintype "passive"))
      (node (ref "EC4") (pin "2") (pinfunction "2_2") (pintype "passive"))
      (node (ref "EC7") (pin "2") (pinfunction "2_2") (pintype "passive"))
      (node (ref "EC8") (pin "2") (pinfunction "2_2") (pintype "passive"))
      (node (ref "EC9") (pin "2") (pinfunction "2_2") (pintype "passive"))
      (node (ref "J11") (pin "4") (pinfunction "GND_4") (pintype "power_in"))
      (node (ref "J11") (pin "5") (pinfunction "SHLD_5") (pintype "passive"))
      (node (ref "J11") (pin "6") (pinfunction "SHLD_6") (pintype "passive"))
      (node (ref "J12") (pin "4") (pinfunction "GND_4") (pintype "power_in"))
      (node (ref "J12") (pin "5") (pinfunction "SHLD_5") (pintype "passive"))
      (node (ref "J12") (pin "6") (pinfunction "SHLD_6") (pintype "passive"))
      (node (ref "J13") (pin "2") (pinfunction "+_2") (pintype "passive"))
      (node (ref "J4") (pin "1") (pinfunction "1_1") (pintype "passive"))
      (node (ref "J5") (pin "14") (pinfunction "14_14") (pintype "passive"))
      (node (ref "J5") (pin "20") (pinfunction "20_20") (pintype "passive"))
      (node (ref "J5") (pin "25") (pinfunction "25_25") (pintype "passive"))
      (node (ref "J5") (pin "30") (pinfunction "30_30") (pintype "passive"))
      (node (ref "J5") (pin "34") (pinfunction "34_34") (pintype "passive"))
      (node (ref "J5") (pin "39") (pinfunction "39_39") (pintype "passive"))
      (node (ref "J5") (pin "6") (pinfunction "6_6") (pintype "passive"))
      (node (ref "J5") (pin "9") (pinfunction "9_9") (pintype "passive"))
      (node (ref "J6") (pin "13") (pinfunction "13_13") (pintype "passive"))
      (node (ref "J6") (pin "20") (pinfunction "20_20") (pintype "passive"))
      (node (ref "J6") (pin "5") (pinfunction "5_5") (pintype "passive"))
      (node (ref "J7") (pin "11") (pinfunction "11_11") (pintype "passive"))
      (node (ref "J7") (pin "14") (pinfunction "14_14") (pintype "passive"))
      (node (ref "J7") (pin "18") (pinfunction "18_18") (pintype "passive"))
      (node (ref "J7") (pin "4") (pinfunction "4_4") (pintype "passive"))
      (node (ref "J7") (pin "6") (pinfunction "6_6") (pintype "passive"))
      (node (ref "K1") (pin "1") (pinfunction "1_1") (pintype "passive"))
      (node (ref "K2") (pin "1") (pinfunction "1_1") (pintype "passive"))
      (node (ref "R15") (pin "1") (pinfunction "1_1") (pintype "passive"))
      (node (ref "R18") (pin "1") (pinfunction "1_1") (pintype "passive"))
      (node (ref "R19") (pin "1") (pinfunction "1_1") (pintype "passive"))
      (node (ref "R22") (pin "1") (pinfunction "1_1") (pintype "passive"))
      (node (ref "R23") (pin "1") (pinfunction "1_1") (pintype "passive"))
      (node (ref "R26") (pin "1") (pinfunction "1_1") (pintype "passive"))
      (node (ref "R5") (pin "1") (pinfunction "1_1") (pintype "passive"))
      (node (ref "U1") (pin "23") (pinfunction "VSS_1_23") (pintype "power_in"))
      (node (ref "U1") (pin "35") (pinfunction "VSS_2_35") (pintype "power_in"))
      (node (ref "U1") (pin "44") (pinfunction "BOOT0_44") (pintype "input"))
      (node (ref "U1") (pin "47") (pinfunction "VSS_3_47") (pintype "power_in"))
      (node (ref "U1") (pin "8") (pinfunction "VSSA_8") (pintype "power_in"))
      (node (ref "U3") (pin "1") (pinfunction "GND_1") (pintype "passive"))
      (node (ref "U6") (pin "0") (pinfunction "PAD_0") (pintype "passive"))
      (node (ref "U6") (pin "15") (pinfunction "AGND_15") (pintype "passive"))
      (node (ref "U6") (pin "4") (pinfunction "GND_4") (pintype "passive"))
      (node (ref "U7") (pin "0") (pinfunction "PAD_0") (pintype "passive"))
      (node (ref "U7") (pin "15") (pinfunction "AGND_15") (pintype "passive"))
      (node (ref "U7") (pin "4") (pinfunction "GND_4") (pintype "passive"))
    )
    (net (code "61") (name "GNDD") (class "Default")
      (node (ref "C13") (pin "1") (pinfunction "1_1") (pintype "passive"))
      (node (ref "PHONE1") (pin "3") (pinfunction "COM_3") (pintype "passive"))
      (node (ref "R15") (pin "2") (pinfunction "2_2") (pintype "passive"))
      (node (ref "S1") (pin "1") (pinfunction "A1_1") (pintype "passive"))
      (node (ref "S1") (pin "2") (pinfunction "A2_2") (pintype "passive"))
      (node (ref "U5") (pin "7") (pinfunction "GND_7") (pintype "passive"))
    )
    (net (code "62") (name "GNDS") (class "Default")
      (node (ref "D1") (pin "A") (pinfunction "A_A") (pintype "passive"))
      (node (ref "D3") (pin "A") (pinfunction "A_A") (pintype "passive"))
      (node (ref "EC1") (pin "2") (pinfunction "2_2") (pintype "passive"))
      (node (ref "EC2") (pin "2") (pinfunction "2_2") (pintype "passive"))
      (node (ref "EC3") (pin "2") (pinfunction "2_2") (pintype "passive"))
      (node (ref "EC5") (pin "2") (pinfunction "2_2") (pintype "passive"))
      (node (ref "EC6") (pin "2") (pinfunction "2_2") (pintype "passive"))
      (node (ref "J8") (pin "5") (pinfunction "5_5") (pintype "passive"))
      (node (ref "J8") (pin "6") (pinfunction "6_6") (pintype "passive"))
      (node (ref "R26") (pin "2") (pinfunction "2_2") (pintype "passive"))
      (node (ref "R3") (pin "1") (pinfunction "1_1") (pintype "passive"))
      (node (ref "U2") (pin "3") (pinfunction "GND_3") (pintype "power_in"))
      (node (ref "U2") (pin "5") (pinfunction "~{ON}/OFF_5") (pintype "input"))
      (node (ref "U2") (pin "6") (pinfunction "GND_6") (pintype "power_in"))
      (node (ref "U4") (pin "3") (pinfunction "GND_3") (pintype "power_in"))
      (node (ref "U4") (pin "5") (pinfunction "~{ON}/OFF_5") (pintype "passive"))
    )
    (net (code "63") (name "Net-(C11-Pad1)") (class "Default")
      (node (ref "C11") (pin "1") (pinfunction "1_1") (pintype "passive"))
      (node (ref "R12") (pin "2") (pinfunction "2_2") (pintype "passive"))
    )
    (net (code "64") (name "Net-(C12-Pad1)") (class "Default")
      (node (ref "C12") (pin "1") (pinfunction "1_1") (pintype "passive"))
      (node (ref "R14") (pin "2") (pinfunction "2_2") (pintype "passive"))
    )
    (net (code "65") (name "Net-(C15-Pad2)") (class "Default")
      (node (ref "C15") (pin "2") (pinfunction "2_2") (pintype "passive"))
      (node (ref "L4") (pin "1") (pinfunction "1_1") (pintype "passive"))
      (node (ref "R24") (pin "1") (pinfunction "1_1") (pintype "passive"))
      (node (ref "U6") (pin "20") (pinfunction "LX_20") (pintype "passive"))
      (node (ref "U6") (pin "21") (pinfunction "LX_21") (pintype "passive"))
      (node (ref "U6") (pin "22") (pinfunction "LX_22") (pintype "passive"))
      (node (ref "U6") (pin "23") (pinfunction "LX_23") (pintype "passive"))
    )
    (net (code "66") (name "Net-(C22-Pad2)") (class "Default")
      (node (ref "C22") (pin "2") (pinfunction "2_2") (pintype "passive"))
      (node (ref "L5") (pin "1") (pinfunction "1_1") (pintype "passive"))
      (node (ref "R25") (pin "1") (pinfunction "1_1") (pintype "passive"))
      (node (ref "U7") (pin "20") (pinfunction "LX_20") (pintype "passive"))
      (node (ref "U7") (pin "21") (pinfunction "LX_21") (pintype "passive"))
      (node (ref "U7") (pin "22") (pinfunction "LX_22") (pintype "passive"))
      (node (ref "U7") (pin "23") (pinfunction "LX_23") (pintype "passive"))
    )
    (net (code "67") (name "Net-(C29-Pad2)") (class "Default")
      (node (ref "C29") (pin "2") (pinfunction "2_2") (pintype "passive"))
      (node (ref "R24") (pin "2") (pinfunction "2_2") (pintype "passive"))
    )
    (net (code "68") (name "Net-(C30-Pad2)") (class "Default")
      (node (ref "C30") (pin "2") (pinfunction "2_2") (pintype "passive"))
      (node (ref "R25") (pin "2") (pinfunction "2_2") (pintype "passive"))
    )
    (net (code "69") (name "Net-(D2-PadA)") (class "Default")
      (node (ref "D2") (pin "A") (pinfunction "A_A") (pintype "passive"))
      (node (ref "R7") (pin "1") (pinfunction "1_1") (pintype "passive"))
    )
    (net (code "70") (name "Net-(D4-PadA)") (class "Default")
      (node (ref "D4") (pin "A") (pinfunction "A_A") (pintype "passive"))
      (node (ref "R8") (pin "1") (pinfunction "1_1") (pintype "passive"))
    )
    (net (code "71") (name "Net-(D5-PadA)") (class "Default")
      (node (ref "D5") (pin "A") (pinfunction "A_A") (pintype "passive"))
      (node (ref "R11") (pin "1") (pinfunction "1_1") (pintype "passive"))
    )
    (net (code "72") (name "Net-(D6-PadA)") (class "Default")
      (node (ref "D6") (pin "A") (pinfunction "A_A") (pintype "passive"))
      (node (ref "R13") (pin "1") (pinfunction "1_1") (pintype "passive"))
    )
    (net (code "73") (name "Net-(D7-PadA)") (class "Default")
      (node (ref "D7") (pin "A") (pinfunction "A_A") (pintype "passive"))
      (node (ref "R17") (pin "1") (pinfunction "1_1") (pintype "passive"))
    )
    (net (code "74") (name "Net-(D9-PadA)") (class "Default")
      (node (ref "D9") (pin "A") (pinfunction "A_A") (pintype "passive"))
      (node (ref "R21") (pin "1") (pinfunction "1_1") (pintype "passive"))
    )
    (net (code "75") (name "Net-(J11-D+)") (class "Default")
      (node (ref "J11") (pin "3") (pinfunction "D+_3") (pintype "input"))
      (node (ref "U6") (pin "8") (pinfunction "DP_8") (pintype "passive"))
    )
    (net (code "76") (name "Net-(J11-D-)") (class "Default")
      (node (ref "J11") (pin "2") (pinfunction "D-_2") (pintype "input"))
      (node (ref "U6") (pin "7") (pinfunction "DM_7") (pintype "passive"))
    )
    (net (code "77") (name "Net-(J11-VBUS)") (class "Default")
      (node (ref "C17") (pin "2") (pinfunction "2_2") (pintype "passive"))
      (node (ref "C21") (pin "2") (pinfunction "2_2") (pintype "passive"))
      (node (ref "J11") (pin "1") (pinfunction "VBUS_1") (pintype "power_in"))
      (node (ref "R16") (pin "2") (pinfunction "2_2") (pintype "passive"))
      (node (ref "R17") (pin "2") (pinfunction "2_2") (pintype "passive"))
      (node (ref "R18") (pin "2") (pinfunction "2_2") (pintype "passive"))
      (node (ref "U6") (pin "13") (pinfunction "VOUT_13") (pintype "passive"))
    )
    (net (code "78") (name "Net-(J12-D+)") (class "Default")
      (node (ref "J12") (pin "3") (pinfunction "D+_3") (pintype "input"))
      (node (ref "U7") (pin "8") (pinfunction "DP_8") (pintype "passive"))
    )
    (net (code "79") (name "Net-(J12-D-)") (class "Default")
      (node (ref "J12") (pin "2") (pinfunction "D-_2") (pintype "input"))
      (node (ref "U7") (pin "7") (pinfunction "DM_7") (pintype "passive"))
    )
    (net (code "80") (name "Net-(J12-VBUS)") (class "Default")
      (node (ref "C24") (pin "2") (pinfunction "2_2") (pintype "passive"))
      (node (ref "C28") (pin "2") (pinfunction "2_2") (pintype "passive"))
      (node (ref "J12") (pin "1") (pinfunction "VBUS_1") (pintype "power_in"))
      (node (ref "R20") (pin "2") (pinfunction "2_2") (pintype "passive"))
      (node (ref "R21") (pin "2") (pinfunction "2_2") (pintype "passive"))
      (node (ref "R22") (pin "2") (pinfunction "2_2") (pintype "passive"))
      (node (ref "U7") (pin "13") (pinfunction "VOUT_13") (pintype "passive"))
    )
    (net (code "81") (name "Net-(PHONE1-CHL)") (class "Default")
      (node (ref "C11") (pin "2") (pinfunction "2_2") (pintype "passive"))
      (node (ref "PHONE1") (pin "1") (pinfunction "CHL_1") (pintype "passive"))
    )
    (net (code "82") (name "Net-(PHONE1-CHR)") (class "Default")
      (node (ref "C12") (pin "2") (pinfunction "2_2") (pintype "passive"))
      (node (ref "PHONE1") (pin "2") (pinfunction "CHR_2") (pintype "passive"))
    )
    (net (code "83") (name "Net-(R2-CCW)") (class "Default")
      (node (ref "R2") (pin "1") (pinfunction "CCW_1") (pintype "passive"))
      (node (ref "R2") (pin "2") (pinfunction "WIPER_2") (pintype "passive"))
      (node (ref "R3") (pin "2") (pinfunction "2_2") (pintype "passive"))
      (node (ref "U2") (pin "4") (pinfunction "Feedback_4") (pintype "passive"))
    )
    (net (code "84") (name "Net-(R2-CW)") (class "Default")
      (node (ref "EC2") (pin "1") (pinfunction "1_1") (pintype "passive"))
      (node (ref "L1") (pin "2") (pinfunction "2_2") (pintype "passive"))
      (node (ref "L2") (pin "1") (pinfunction "1_1") (pintype "passive"))
      (node (ref "R2") (pin "3") (pinfunction "CW_3") (pintype "passive"))
    )
    (net (code "85") (name "Net-(S1-B1)") (class "Default")
      (node (ref "R9") (pin "1") (pinfunction "1_1") (pintype "passive"))
      (node (ref "S1") (pin "4") (pinfunction "B1_4") (pintype "passive"))
      (node (ref "U5") (pin "1") (pinfunction "SD_1") (pintype "passive"))
    )
    (net (code "86") (name "Net-(S1-B2)") (class "Default")
      (node (ref "R10") (pin "1") (pinfunction "1_1") (pintype "passive"))
      (node (ref "S1") (pin "3") (pinfunction "B2_3") (pintype "passive"))
      (node (ref "U5") (pin "3") (pinfunction "MODE_3") (pintype "passive"))
    )
    (net (code "87") (name "Net-(U1A-PB0)") (class "Default")
      (node (ref "J2") (pin "1") (pinfunction "1_1") (pintype "passive"))
      (node (ref "U1") (pin "18") (pinfunction "PB0_18") (pintype "bidirectional"))
    )
    (net (code "88") (name "Net-(U1A-PB1)") (class "Default")
      (node (ref "J2") (pin "2") (pinfunction "2_2") (pintype "passive"))
      (node (ref "U1") (pin "19") (pinfunction "PB1_19") (pintype "bidirectional"))
    )
    (net (code "89") (name "Net-(U1A-PB2)") (class "Default")
      (node (ref "J2") (pin "3") (pinfunction "3_3") (pintype "passive"))
      (node (ref "U1") (pin "20") (pinfunction "PB2_20") (pintype "bidirectional"))
    )
    (net (code "90") (name "Net-(U1A-PB3)") (class "Default")
      (node (ref "J2") (pin "4") (pinfunction "4_4") (pintype "passive"))
      (node (ref "U1") (pin "39") (pinfunction "PB3_39") (pintype "bidirectional"))
    )
    (net (code "91") (name "Net-(U1A-PB4)") (class "Default")
      (node (ref "J2") (pin "5") (pinfunction "5_5") (pintype "passive"))
      (node (ref "U1") (pin "40") (pinfunction "PB4_40") (pintype "bidirectional"))
    )
    (net (code "92") (name "Net-(U1A-PB5)") (class "Default")
      (node (ref "J2") (pin "6") (pinfunction "6_6") (pintype "passive"))
      (node (ref "U1") (pin "41") (pinfunction "PB5_41") (pintype "bidirectional"))
    )
    (net (code "93") (name "Net-(U1A-PB6)") (class "Default")
      (node (ref "J2") (pin "7") (pinfunction "7_7") (pintype "passive"))
      (node (ref "U1") (pin "42") (pinfunction "PB6_42") (pintype "bidirectional"))
    )
    (net (code "94") (name "Net-(U1A-PB7)") (class "Default")
      (node (ref "J2") (pin "8") (pinfunction "8_8") (pintype "passive"))
      (node (ref "U1") (pin "43") (pinfunction "PB7_43") (pintype "bidirectional"))
    )
    (net (code "95") (name "Net-(U1A-PD0-OSC_IN)") (class "Default")
      (node (ref "C2") (pin "2") (pinfunction "2_2") (pintype "passive"))
      (node (ref "R6") (pin "2") (pinfunction "2_2") (pintype "passive"))
      (node (ref "U1") (pin "5") (pinfunction "PD0-OSC_IN_5") (pintype "bidirectional"))
      (node (ref "X1") (pin "2") (pinfunction "2_2") (pintype "passive"))
    )
    (net (code "96") (name "Net-(U1A-PD1-OSC_OUT)") (class "Default")
      (node (ref "C5") (pin "2") (pinfunction "2_2") (pintype "passive"))
      (node (ref "R6") (pin "1") (pinfunction "1_1") (pintype "passive"))
      (node (ref "U1") (pin "6") (pinfunction "PD1-OSC_OUT_6") (pintype "bidirectional"))
      (node (ref "X1") (pin "1") (pinfunction "1_1") (pintype "passive"))
    )
    (net (code "97") (name "Net-(U2-Output)") (class "Default")
      (node (ref "D1") (pin "K") (pinfunction "K_K") (pintype "passive"))
      (node (ref "L1") (pin "1") (pinfunction "1_1") (pintype "passive"))
      (node (ref "U2") (pin "2") (pinfunction "Output_2") (pintype "output"))
    )
    (net (code "98") (name "Net-(U4-OUT)") (class "Default")
      (node (ref "D3") (pin "K") (pinfunction "K_K") (pintype "passive"))
      (node (ref "L3") (pin "1") (pinfunction "1_1") (pintype "passive"))
      (node (ref "U4") (pin "2") (pinfunction "OUT_2") (pintype "power_in"))
    )
    (net (code "99") (name "Net-(U5-Byp)") (class "Default")
      (node (ref "C13") (pin "2") (pinfunction "2_2") (pintype "passive"))
      (node (ref "U5") (pin "2") (pinfunction "Byp_2") (pintype "passive"))
    )
    (net (code "100") (name "Net-(U5-IN)") (class "Default")
      (node (ref "R12") (pin "1") (pinfunction "1_1") (pintype "passive"))
      (node (ref "R14") (pin "1") (pinfunction "1_1") (pintype "passive"))
      (node (ref "U5") (pin "4") (pinfunction "IN_4") (pintype "passive"))
    )
    (net (code "101") (name "Net-(U5-VON)") (class "Default")
      (node (ref "U5") (pin "5") (pinfunction "VON_5") (pintype "passive"))
      (node (ref "XH1") (pin "2") (pinfunction "2_2") (pintype "passive"))
    )
    (net (code "102") (name "Net-(U5-VOP)") (class "Default")
      (node (ref "U5") (pin "8") (pinfunction "VOP_8") (pintype "passive"))
      (node (ref "XH1") (pin "1") (pinfunction "1_1") (pintype "passive"))
    )
    (net (code "103") (name "Net-(U6-BST)") (class "Default")
      (node (ref "C15") (pin "1") (pinfunction "1_1") (pintype "passive"))
      (node (ref "U6") (pin "24") (pinfunction "BST_24") (pintype "passive"))
    )
    (net (code "104") (name "Net-(U6-FS)") (class "Default")
      (node (ref "R19") (pin "2") (pinfunction "2_2") (pintype "passive"))
      (node (ref "U6") (pin "6") (pinfunction "FS_6") (pintype "passive"))
    )
    (net (code "105") (name "Net-(U6-VSP)") (class "Default")
      (node (ref "C16") (pin "2") (pinfunction "2_2") (pintype "passive"))
      (node (ref "C20") (pin "2") (pinfunction "2_2") (pintype "passive"))
      (node (ref "EC8") (pin "1") (pinfunction "1_1") (pintype "passive"))
      (node (ref "L4") (pin "2") (pinfunction "2_2") (pintype "passive"))
      (node (ref "R16") (pin "1") (pinfunction "1_1") (pintype "passive"))
      (node (ref "U6") (pin "14") (pinfunction "VSP_14") (pintype "passive"))
    )
    (net (code "106") (name "Net-(U7-BST)") (class "Default")
      (node (ref "C22") (pin "1") (pinfunction "1_1") (pintype "passive"))
      (node (ref "U7") (pin "24") (pinfunction "BST_24") (pintype "passive"))
    )
    (net (code "107") (name "Net-(U7-FS)") (class "Default")
      (node (ref "R23") (pin "2") (pinfunction "2_2") (pintype "passive"))
      (node (ref "U7") (pin "6") (pinfunction "FS_6") (pintype "passive"))
    )
    (net (code "108") (name "Net-(U7-VSP)") (class "Default")
      (node (ref "C23") (pin "2") (pinfunction "2_2") (pintype "passive"))
      (node (ref "C27") (pin "2") (pinfunction "2_2") (pintype "passive"))
      (node (ref "EC10") (pin "1") (pinfunction "1_1") (pintype "passive"))
      (node (ref "L5") (pin "2") (pinfunction "2_2") (pintype "passive"))
      (node (ref "R20") (pin "1") (pinfunction "1_1") (pintype "passive"))
      (node (ref "U7") (pin "14") (pinfunction "VSP_14") (pintype "passive"))
    )
    (net (code "109") (name "Servo_Voltage") (class "Default")
      (node (ref "EC3") (pin "1") (pinfunction "1_1") (pintype "passive"))
      (node (ref "J8") (pin "3") (pinfunction "3_3") (pintype "passive"))
      (node (ref "J8") (pin "4") (pinfunction "4_4") (pintype "passive"))
      (node (ref "L2") (pin "2") (pinfunction "2_2") (pintype "passive"))
    )
    (net (code "110") (name "unconnected-(U1A-PC13-TAMPER-RTC-Pad2)") (class "Default")
      (node (ref "U1") (pin "2") (pinfunction "PC13-TAMPER-RTC_2") (pintype "bidirectional"))
    )
    (net (code "111") (name "unconnected-(U1A-PC14-OSC32_IN-Pad3)") (class "Default")
      (node (ref "U1") (pin "3") (pinfunction "PC14-OSC32_IN_3") (pintype "bidirectional"))
    )
    (net (code "112") (name "unconnected-(U1A-PC15-OSC32_OUT-Pad4)") (class "Default")
      (node (ref "U1") (pin "4") (pinfunction "PC15-OSC32_OUT_4") (pintype "bidirectional"))
    )
    (net (code "113") (name "unconnected-(U6-CC1-Pad9)") (class "Default")
      (node (ref "U6") (pin "9") (pinfunction "CC1_9") (pintype "passive+no_connect"))
    )
    (net (code "114") (name "unconnected-(U6-CC2-Pad10)") (class "Default")
      (node (ref "U6") (pin "10") (pinfunction "CC2_10") (pintype "passive+no_connect"))
    )
    (net (code "115") (name "unconnected-(U6-NC-Pad1)") (class "Default")
      (node (ref "U6") (pin "1") (pinfunction "NC_1") (pintype "passive+no_connect"))
    )
    (net (code "116") (name "unconnected-(U6-NC-Pad5)") (class "Default")
      (node (ref "U6") (pin "5") (pinfunction "NC_5") (pintype "passive+no_connect"))
    )
    (net (code "117") (name "unconnected-(U6-NC-Pad11)") (class "Default")
      (node (ref "U6") (pin "11") (pinfunction "NC_11") (pintype "passive+no_connect"))
    )
    (net (code "118") (name "unconnected-(U6-NC-Pad12)") (class "Default")
      (node (ref "U6") (pin "12") (pinfunction "NC_12") (pintype "passive+no_connect"))
    )
    (net (code "119") (name "unconnected-(U6-NDRV-Pad19)") (class "Default")
      (node (ref "U6") (pin "19") (pinfunction "NDRV_19") (pintype "passive+no_connect"))
    )
    (net (code "120") (name "unconnected-(U7-CC1-Pad9)") (class "Default")
      (node (ref "U7") (pin "9") (pinfunction "CC1_9") (pintype "passive+no_connect"))
    )
    (net (code "121") (name "unconnected-(U7-CC2-Pad10)") (class "Default")
      (node (ref "U7") (pin "10") (pinfunction "CC2_10") (pintype "passive+no_connect"))
    )
    (net (code "122") (name "unconnected-(U7-NC-Pad1)") (class "Default")
      (node (ref "U7") (pin "1") (pinfunction "NC_1") (pintype "passive+no_connect"))
    )
    (net (code "123") (name "unconnected-(U7-NC-Pad5)") (class "Default")
      (node (ref "U7") (pin "5") (pinfunction "NC_5") (pintype "passive+no_connect"))
    )
    (net (code "124") (name "unconnected-(U7-NC-Pad11)") (class "Default")
      (node (ref "U7") (pin "11") (pinfunction "NC_11") (pintype "passive+no_connect"))
    )
    (net (code "125") (name "unconnected-(U7-NC-Pad12)") (class "Default")
      (node (ref "U7") (pin "12") (pinfunction "NC_12") (pintype "passive+no_connect"))
    )
    (net (code "126") (name "unconnected-(U7-NDRV-Pad19)") (class "Default")
      (node (ref "U7") (pin "19") (pinfunction "NDRV_19") (pintype "passive+no_connect"))
    )
  )
)
